# cfide-adapter.net
KiCad netlist of a schematic drawn in EAGLE
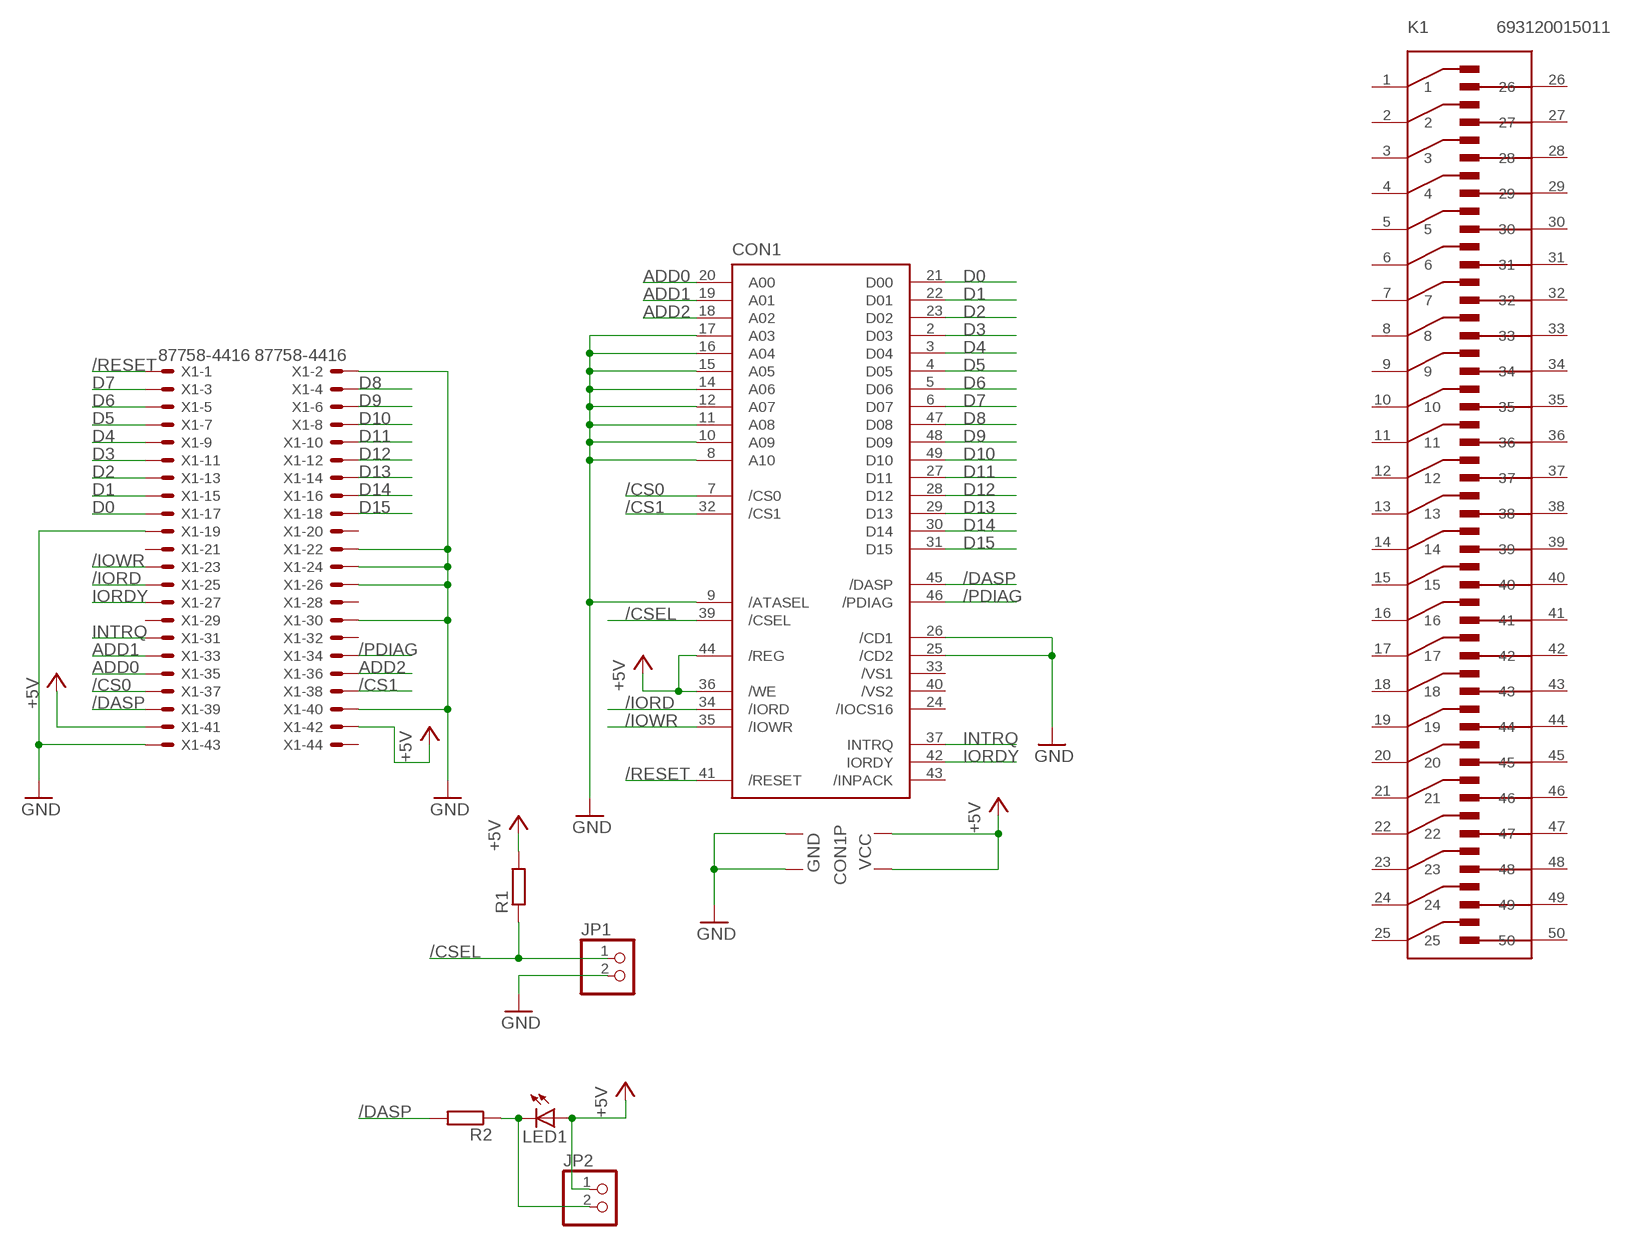
[diagram p0: schematic, sheet 1]

(export (version "E")
  (design (tool "Eeschema 10.0.6"))
  (components
    (comp (ref "CON1")
      (value "CF-CARD-IDE_MODE")
      (footprint "eagle-import:MI20-50PD-SF")
      (libsource (lib "eagle-import") (part "CF-CARD-IDE_MODE"))
    )
    (comp (ref "JP1")
      (value "HEADER-1X2ROUND")
      (footprint "eagle-import:1X02_ROUND")
      (libsource (lib "eagle-import") (part "HEADER-1X2ROUND"))
    )
    (comp (ref "JP2")
      (value "HEADER-1X2ROUND")
      (footprint "eagle-import:1X02_ROUND")
      (libsource (lib "eagle-import") (part "HEADER-1X2ROUND"))
    )
    (comp (ref "K1")
      (value "693120015011")
      (footprint "eagle-import:693120015011")
      (libsource (lib "eagle-import") (part "693120015011"))
    )
    (comp (ref "LED1")
      (value "LEDCHIP-LED0603")
      (footprint "eagle-import:CHIP-LED0603")
      (libsource (lib "eagle-import") (part "LEDCHIP-LED0603"))
    )
    (comp (ref "R1")
      (value "R-EU_R0603")
      (footprint "eagle-import:R0603")
      (libsource (lib "eagle-import") (part "R-EU_R0603"))
    )
    (comp (ref "R2")
      (value "R-EU_R0603")
      (footprint "eagle-import:R0603")
      (libsource (lib "eagle-import") (part "R-EU_R0603"))
    )
    (comp (ref "X1")
      (value "87758-4416")
      (footprint "eagle-import:87758-4416")
      (fields (field (name "MF") "MOLEX"))
      (libsource (lib "eagle-import") (part "87758-4416"))
    )
  )
  (nets
    (net (code "1") (name "+5V") (class "Default")
      (node (ref "CON1") (pin "13") (pinfunction "VCC2_13") (pintype "power_in"))
      (node (ref "CON1") (pin "36") (pinfunction "/WE_36") (pintype "input"))
      (node (ref "CON1") (pin "38") (pinfunction "VCC1_38") (pintype "power_in"))
      (node (ref "CON1") (pin "44") (pinfunction "/REG_44") (pintype "input"))
      (node (ref "JP2") (pin "1") (pinfunction "1_1") (pintype "passive"))
      (node (ref "LED1") (pin "A") (pinfunction "A_A") (pintype "passive"))
      (node (ref "R1") (pin "2") (pinfunction "2_2") (pintype "passive"))
      (node (ref "X1") (pin "41") (pinfunction "S_41") (pintype "passive"))
      (node (ref "X1") (pin "42") (pinfunction "S_42") (pintype "passive"))
    )
    (net (code "2") (name "/ADD0") (class "Default")
      (node (ref "CON1") (pin "20") (pinfunction "A00_20") (pintype "input"))
      (node (ref "X1") (pin "35") (pinfunction "S_35") (pintype "passive"))
    )
    (net (code "3") (name "/ADD1") (class "Default")
      (node (ref "CON1") (pin "19") (pinfunction "A01_19") (pintype "input"))
      (node (ref "X1") (pin "33") (pinfunction "S_33") (pintype "passive"))
    )
    (net (code "4") (name "/ADD2") (class "Default")
      (node (ref "CON1") (pin "18") (pinfunction "A02_18") (pintype "input"))
      (node (ref "X1") (pin "36") (pinfunction "S_36") (pintype "passive"))
    )
    (net (code "5") (name "/D0") (class "Default")
      (node (ref "CON1") (pin "21") (pinfunction "D00_21") (pintype "bidirectional"))
      (node (ref "X1") (pin "17") (pinfunction "S_17") (pintype "passive"))
    )
    (net (code "6") (name "/D1") (class "Default")
      (node (ref "CON1") (pin "22") (pinfunction "D01_22") (pintype "bidirectional"))
      (node (ref "X1") (pin "15") (pinfunction "S_15") (pintype "passive"))
    )
    (net (code "7") (name "/D2") (class "Default")
      (node (ref "CON1") (pin "23") (pinfunction "D02_23") (pintype "bidirectional"))
      (node (ref "X1") (pin "13") (pinfunction "S_13") (pintype "passive"))
    )
    (net (code "8") (name "/D3") (class "Default")
      (node (ref "CON1") (pin "2") (pinfunction "D03_2") (pintype "bidirectional"))
      (node (ref "X1") (pin "11") (pinfunction "S_11") (pintype "passive"))
    )
    (net (code "9") (name "/D4") (class "Default")
      (node (ref "CON1") (pin "3") (pinfunction "D04_3") (pintype "bidirectional"))
      (node (ref "X1") (pin "9") (pinfunction "S_9") (pintype "passive"))
    )
    (net (code "10") (name "/D5") (class "Default")
      (node (ref "CON1") (pin "4") (pinfunction "D05_4") (pintype "bidirectional"))
      (node (ref "X1") (pin "7") (pinfunction "S_7") (pintype "passive"))
    )
    (net (code "11") (name "/D6") (class "Default")
      (node (ref "CON1") (pin "5") (pinfunction "D06_5") (pintype "bidirectional"))
      (node (ref "X1") (pin "5") (pinfunction "S_5") (pintype "passive"))
    )
    (net (code "12") (name "/D7") (class "Default")
      (node (ref "CON1") (pin "6") (pinfunction "D07_6") (pintype "bidirectional"))
      (node (ref "X1") (pin "3") (pinfunction "S_3") (pintype "passive"))
    )
    (net (code "13") (name "/D8") (class "Default")
      (node (ref "CON1") (pin "47") (pinfunction "D08_47") (pintype "bidirectional"))
      (node (ref "X1") (pin "4") (pinfunction "S_4") (pintype "passive"))
    )
    (net (code "14") (name "/D9") (class "Default")
      (node (ref "CON1") (pin "48") (pinfunction "D09_48") (pintype "bidirectional"))
      (node (ref "X1") (pin "6") (pinfunction "S_6") (pintype "passive"))
    )
    (net (code "15") (name "/D10") (class "Default")
      (node (ref "CON1") (pin "49") (pinfunction "D10_49") (pintype "bidirectional"))
      (node (ref "X1") (pin "8") (pinfunction "S_8") (pintype "passive"))
    )
    (net (code "16") (name "/D11") (class "Default")
      (node (ref "CON1") (pin "27") (pinfunction "D11_27") (pintype "bidirectional"))
      (node (ref "X1") (pin "10") (pinfunction "S_10") (pintype "passive"))
    )
    (net (code "17") (name "/D12") (class "Default")
      (node (ref "CON1") (pin "28") (pinfunction "D12_28") (pintype "bidirectional"))
      (node (ref "X1") (pin "12") (pinfunction "S_12") (pintype "passive"))
    )
    (net (code "18") (name "/D13") (class "Default")
      (node (ref "CON1") (pin "29") (pinfunction "D13_29") (pintype "bidirectional"))
      (node (ref "X1") (pin "14") (pinfunction "S_14") (pintype "passive"))
    )
    (net (code "19") (name "/D14") (class "Default")
      (node (ref "CON1") (pin "30") (pinfunction "D14_30") (pintype "bidirectional"))
      (node (ref "X1") (pin "16") (pinfunction "S_16") (pintype "passive"))
    )
    (net (code "20") (name "/D15") (class "Default")
      (node (ref "CON1") (pin "31") (pinfunction "D15_31") (pintype "bidirectional"))
      (node (ref "X1") (pin "18") (pinfunction "S_18") (pintype "passive"))
    )
    (net (code "21") (name "/INTRQ") (class "Default")
      (node (ref "CON1") (pin "37") (pinfunction "INTRQ_37") (pintype "output"))
      (node (ref "X1") (pin "31") (pinfunction "S_31") (pintype "passive"))
    )
    (net (code "22") (name "/IORDY") (class "Default")
      (node (ref "CON1") (pin "42") (pinfunction "IORDY_42") (pintype "output"))
      (node (ref "X1") (pin "27") (pinfunction "S_27") (pintype "passive"))
    )
    (net (code "23") (name "/{slash}CS0") (class "Default")
      (node (ref "CON1") (pin "7") (pinfunction "/CS0_7") (pintype "input"))
      (node (ref "X1") (pin "37") (pinfunction "S_37") (pintype "passive"))
    )
    (net (code "24") (name "/{slash}CS1") (class "Default")
      (node (ref "CON1") (pin "32") (pinfunction "/CS1_32") (pintype "input"))
      (node (ref "X1") (pin "38") (pinfunction "S_38") (pintype "passive"))
    )
    (net (code "25") (name "/{slash}CSEL") (class "Default")
      (node (ref "CON1") (pin "39") (pinfunction "/CSEL_39") (pintype "input"))
      (node (ref "JP1") (pin "1") (pinfunction "1_1") (pintype "passive"))
      (node (ref "R1") (pin "1") (pinfunction "1_1") (pintype "passive"))
    )
    (net (code "26") (name "/{slash}DASP") (class "Default")
      (node (ref "CON1") (pin "45") (pinfunction "/DASP_45") (pintype "bidirectional"))
      (node (ref "R2") (pin "2") (pinfunction "2_2") (pintype "passive"))
      (node (ref "X1") (pin "39") (pinfunction "S_39") (pintype "passive"))
    )
    (net (code "27") (name "/{slash}IORD") (class "Default")
      (node (ref "CON1") (pin "34") (pinfunction "/IORD_34") (pintype "input"))
      (node (ref "X1") (pin "25") (pinfunction "S_25") (pintype "passive"))
    )
    (net (code "28") (name "/{slash}IOWR") (class "Default")
      (node (ref "CON1") (pin "35") (pinfunction "/IOWR_35") (pintype "input"))
      (node (ref "X1") (pin "23") (pinfunction "S_23") (pintype "passive"))
    )
    (net (code "29") (name "/{slash}PDIAG") (class "Default")
      (node (ref "CON1") (pin "46") (pinfunction "/PDIAG_46") (pintype "bidirectional"))
      (node (ref "X1") (pin "34") (pinfunction "S_34") (pintype "passive"))
    )
    (net (code "30") (name "/{slash}RESET") (class "Default")
      (node (ref "CON1") (pin "41") (pinfunction "/RESET_41") (pintype "input"))
      (node (ref "X1") (pin "1") (pinfunction "S_1") (pintype "passive"))
    )
    (net (code "31") (name "GND") (class "Default")
      (node (ref "CON1") (pin "1") (pinfunction "GND1_1") (pintype "power_in"))
      (node (ref "CON1") (pin "10") (pinfunction "A09_10") (pintype "input"))
      (node (ref "CON1") (pin "11") (pinfunction "A08_11") (pintype "input"))
      (node (ref "CON1") (pin "12") (pinfunction "A07_12") (pintype "input"))
      (node (ref "CON1") (pin "14") (pinfunction "A06_14") (pintype "input"))
      (node (ref "CON1") (pin "15") (pinfunction "A05_15") (pintype "input"))
      (node (ref "CON1") (pin "16") (pinfunction "A04_16") (pintype "input"))
      (node (ref "CON1") (pin "17") (pinfunction "A03_17") (pintype "input"))
      (node (ref "CON1") (pin "25") (pinfunction "/CD2_25") (pintype "output"))
      (node (ref "CON1") (pin "26") (pinfunction "/CD1_26") (pintype "output"))
      (node (ref "CON1") (pin "50") (pinfunction "GND2_50") (pintype "power_in"))
      (node (ref "CON1") (pin "8") (pinfunction "A10_8") (pintype "input"))
      (node (ref "CON1") (pin "9") (pinfunction "/ATASEL_9") (pintype "input"))
      (node (ref "JP1") (pin "2") (pinfunction "2_2") (pintype "passive"))
      (node (ref "X1") (pin "19") (pinfunction "S_19") (pintype "passive"))
      (node (ref "X1") (pin "2") (pinfunction "S_2") (pintype "passive"))
      (node (ref "X1") (pin "22") (pinfunction "S_22") (pintype "passive"))
      (node (ref "X1") (pin "24") (pinfunction "S_24") (pintype "passive"))
      (node (ref "X1") (pin "26") (pinfunction "S_26") (pintype "passive"))
      (node (ref "X1") (pin "30") (pinfunction "S_30") (pintype "passive"))
      (node (ref "X1") (pin "40") (pinfunction "S_40") (pintype "passive"))
      (node (ref "X1") (pin "43") (pinfunction "S_43") (pintype "passive"))
    )
    (net (code "32") (name "Net-(JP2-Pad2)") (class "Default")
      (node (ref "JP2") (pin "2") (pinfunction "2_2") (pintype "passive"))
      (node (ref "LED1") (pin "C") (pinfunction "C_C") (pintype "passive"))
      (node (ref "R2") (pin "1") (pinfunction "1_1") (pintype "passive"))
    )
    (net (code "33") (name "unconnected-(CON1A-{slash}INPACK-Pad43)") (class "Default")
      (node (ref "CON1") (pin "43") (pinfunction "/INPACK_43") (pintype "output"))
    )
    (net (code "34") (name "unconnected-(CON1A-{slash}IOCS16-Pad24)") (class "Default")
      (node (ref "CON1") (pin "24") (pinfunction "/IOCS16_24") (pintype "output"))
    )
    (net (code "35") (name "unconnected-(CON1A-{slash}VS1-Pad33)") (class "Default")
      (node (ref "CON1") (pin "33") (pinfunction "/VS1_33") (pintype "output"))
    )
    (net (code "36") (name "unconnected-(CON1A-{slash}VS2-Pad40)") (class "Default")
      (node (ref "CON1") (pin "40") (pinfunction "/VS2_40") (pintype "output"))
    )
    (net (code "37") (name "unconnected-(K1-Pad1)") (class "Default")
      (node (ref "K1") (pin "1") (pinfunction "1_1") (pintype "bidirectional"))
    )
    (net (code "38") (name "unconnected-(K1-Pad2)") (class "Default")
      (node (ref "K1") (pin "2") (pinfunction "2_2") (pintype "bidirectional"))
    )
    (net (code "39") (name "unconnected-(K1-Pad3)") (class "Default")
      (node (ref "K1") (pin "3") (pinfunction "3_3") (pintype "bidirectional"))
    )
    (net (code "40") (name "unconnected-(K1-Pad4)") (class "Default")
      (node (ref "K1") (pin "4") (pinfunction "4_4") (pintype "bidirectional"))
    )
    (net (code "41") (name "unconnected-(K1-Pad5)") (class "Default")
      (node (ref "K1") (pin "5") (pinfunction "5_5") (pintype "bidirectional"))
    )
    (net (code "42") (name "unconnected-(K1-Pad6)") (class "Default")
      (node (ref "K1") (pin "6") (pinfunction "6_6") (pintype "bidirectional"))
    )
    (net (code "43") (name "unconnected-(K1-Pad7)") (class "Default")
      (node (ref "K1") (pin "7") (pinfunction "7_7") (pintype "bidirectional"))
    )
    (net (code "44") (name "unconnected-(K1-Pad8)") (class "Default")
      (node (ref "K1") (pin "8") (pinfunction "8_8") (pintype "bidirectional"))
    )
    (net (code "45") (name "unconnected-(K1-Pad9)") (class "Default")
      (node (ref "K1") (pin "9") (pinfunction "9_9") (pintype "bidirectional"))
    )
    (net (code "46") (name "unconnected-(K1-Pad10)") (class "Default")
      (node (ref "K1") (pin "10") (pinfunction "10_10") (pintype "bidirectional"))
    )
    (net (code "47") (name "unconnected-(K1-Pad11)") (class "Default")
      (node (ref "K1") (pin "11") (pinfunction "11_11") (pintype "bidirectional"))
    )
    (net (code "48") (name "unconnected-(K1-Pad12)") (class "Default")
      (node (ref "K1") (pin "12") (pinfunction "12_12") (pintype "bidirectional"))
    )
    (net (code "49") (name "unconnected-(K1-Pad13)") (class "Default")
      (node (ref "K1") (pin "13") (pinfunction "13_13") (pintype "bidirectional"))
    )
    (net (code "50") (name "unconnected-(K1-Pad14)") (class "Default")
      (node (ref "K1") (pin "14") (pinfunction "14_14") (pintype "bidirectional"))
    )
    (net (code "51") (name "unconnected-(K1-Pad15)") (class "Default")
      (node (ref "K1") (pin "15") (pinfunction "15_15") (pintype "bidirectional"))
    )
    (net (code "52") (name "unconnected-(K1-Pad16)") (class "Default")
      (node (ref "K1") (pin "16") (pinfunction "16_16") (pintype "bidirectional"))
    )
    (net (code "53") (name "unconnected-(K1-Pad17)") (class "Default")
      (node (ref "K1") (pin "17") (pinfunction "17_17") (pintype "bidirectional"))
    )
    (net (code "54") (name "unconnected-(K1-Pad18)") (class "Default")
      (node (ref "K1") (pin "18") (pinfunction "18_18") (pintype "bidirectional"))
    )
    (net (code "55") (name "unconnected-(K1-Pad19)") (class "Default")
      (node (ref "K1") (pin "19") (pinfunction "19_19") (pintype "bidirectional"))
    )
    (net (code "56") (name "unconnected-(K1-Pad20)") (class "Default")
      (node (ref "K1") (pin "20") (pinfunction "20_20") (pintype "bidirectional"))
    )
    (net (code "57") (name "unconnected-(K1-Pad21)") (class "Default")
      (node (ref "K1") (pin "21") (pinfunction "21_21") (pintype "bidirectional"))
    )
    (net (code "58") (name "unconnected-(K1-Pad22)") (class "Default")
      (node (ref "K1") (pin "22") (pinfunction "22_22") (pintype "bidirectional"))
    )
    (net (code "59") (name "unconnected-(K1-Pad23)") (class "Default")
      (node (ref "K1") (pin "23") (pinfunction "23_23") (pintype "bidirectional"))
    )
    (net (code "60") (name "unconnected-(K1-Pad24)") (class "Default")
      (node (ref "K1") (pin "24") (pinfunction "24_24") (pintype "bidirectional"))
    )
    (net (code "61") (name "unconnected-(K1-Pad25)") (class "Default")
      (node (ref "K1") (pin "25") (pinfunction "25_25") (pintype "bidirectional"))
    )
    (net (code "62") (name "unconnected-(K1-Pad26)") (class "Default")
      (node (ref "K1") (pin "26") (pinfunction "26_26") (pintype "bidirectional"))
    )
    (net (code "63") (name "unconnected-(K1-Pad27)") (class "Default")
      (node (ref "K1") (pin "27") (pinfunction "27_27") (pintype "bidirectional"))
    )
    (net (code "64") (name "unconnected-(K1-Pad28)") (class "Default")
      (node (ref "K1") (pin "28") (pinfunction "28_28") (pintype "bidirectional"))
    )
    (net (code "65") (name "unconnected-(K1-Pad29)") (class "Default")
      (node (ref "K1") (pin "29") (pinfunction "29_29") (pintype "bidirectional"))
    )
    (net (code "66") (name "unconnected-(K1-Pad30)") (class "Default")
      (node (ref "K1") (pin "30") (pinfunction "30_30") (pintype "bidirectional"))
    )
    (net (code "67") (name "unconnected-(K1-Pad31)") (class "Default")
      (node (ref "K1") (pin "31") (pinfunction "31_31") (pintype "bidirectional"))
    )
    (net (code "68") (name "unconnected-(K1-Pad32)") (class "Default")
      (node (ref "K1") (pin "32") (pinfunction "32_32") (pintype "bidirectional"))
    )
    (net (code "69") (name "unconnected-(K1-Pad33)") (class "Default")
      (node (ref "K1") (pin "33") (pinfunction "33_33") (pintype "bidirectional"))
    )
    (net (code "70") (name "unconnected-(K1-Pad34)") (class "Default")
      (node (ref "K1") (pin "34") (pinfunction "34_34") (pintype "bidirectional"))
    )
    (net (code "71") (name "unconnected-(K1-Pad35)") (class "Default")
      (node (ref "K1") (pin "35") (pinfunction "35_35") (pintype "bidirectional"))
    )
    (net (code "72") (name "unconnected-(K1-Pad36)") (class "Default")
      (node (ref "K1") (pin "36") (pinfunction "36_36") (pintype "bidirectional"))
    )
    (net (code "73") (name "unconnected-(K1-Pad37)") (class "Default")
      (node (ref "K1") (pin "37") (pinfunction "37_37") (pintype "bidirectional"))
    )
    (net (code "74") (name "unconnected-(K1-Pad38)") (class "Default")
      (node (ref "K1") (pin "38") (pinfunction "38_38") (pintype "bidirectional"))
    )
    (net (code "75") (name "unconnected-(K1-Pad39)") (class "Default")
      (node (ref "K1") (pin "39") (pinfunction "39_39") (pintype "bidirectional"))
    )
    (net (code "76") (name "unconnected-(K1-Pad40)") (class "Default")
      (node (ref "K1") (pin "40") (pinfunction "40_40") (pintype "bidirectional"))
    )
    (net (code "77") (name "unconnected-(K1-Pad41)") (class "Default")
      (node (ref "K1") (pin "41") (pinfunction "41_41") (pintype "bidirectional"))
    )
    (net (code "78") (name "unconnected-(K1-Pad42)") (class "Default")
      (node (ref "K1") (pin "42") (pinfunction "42_42") (pintype "bidirectional"))
    )
    (net (code "79") (name "unconnected-(K1-Pad43)") (class "Default")
      (node (ref "K1") (pin "43") (pinfunction "43_43") (pintype "bidirectional"))
    )
    (net (code "80") (name "unconnected-(K1-Pad44)") (class "Default")
      (node (ref "K1") (pin "44") (pinfunction "44_44") (pintype "bidirectional"))
    )
    (net (code "81") (name "unconnected-(K1-Pad45)") (class "Default")
      (node (ref "K1") (pin "45") (pinfunction "45_45") (pintype "bidirectional"))
    )
    (net (code "82") (name "unconnected-(K1-Pad46)") (class "Default")
      (node (ref "K1") (pin "46") (pinfunction "46_46") (pintype "bidirectional"))
    )
    (net (code "83") (name "unconnected-(K1-Pad47)") (class "Default")
      (node (ref "K1") (pin "47") (pinfunction "47_47") (pintype "bidirectional"))
    )
    (net (code "84") (name "unconnected-(K1-Pad48)") (class "Default")
      (node (ref "K1") (pin "48") (pinfunction "48_48") (pintype "bidirectional"))
    )
    (net (code "85") (name "unconnected-(K1-Pad49)") (class "Default")
      (node (ref "K1") (pin "49") (pinfunction "49_49") (pintype "bidirectional"))
    )
    (net (code "86") (name "unconnected-(K1-Pad50)") (class "Default")
      (node (ref "K1") (pin "50") (pinfunction "50_50") (pintype "bidirectional"))
    )
    (net (code "87") (name "unconnected-(X1AM-S-Pad44)") (class "Default")
      (node (ref "X1") (pin "44") (pinfunction "S_44") (pintype "passive"))
    )
    (net (code "88") (name "unconnected-(X1M-S-Pad20)") (class "Default")
      (node (ref "X1") (pin "20") (pinfunction "S_20") (pintype "passive"))
    )
    (net (code "89") (name "unconnected-(X1N-S-Pad21)") (class "Default")
      (node (ref "X1") (pin "21") (pinfunction "S_21") (pintype "passive"))
    )
    (net (code "90") (name "unconnected-(X1U-S-Pad28)") (class "Default")
      (node (ref "X1") (pin "28") (pinfunction "S_28") (pintype "passive"))
    )
    (net (code "91") (name "unconnected-(X1V-S-Pad29)") (class "Default")
      (node (ref "X1") (pin "29") (pinfunction "S_29") (pintype "passive"))
    )
    (net (code "92") (name "unconnected-(X1Z-S-Pad32)") (class "Default")
      (node (ref "X1") (pin "32") (pinfunction "S_32") (pintype "passive"))
    )
  )
)
